# 03_HMS_Input.net
KiCad netlist of a schematic drawn in Altium Designer
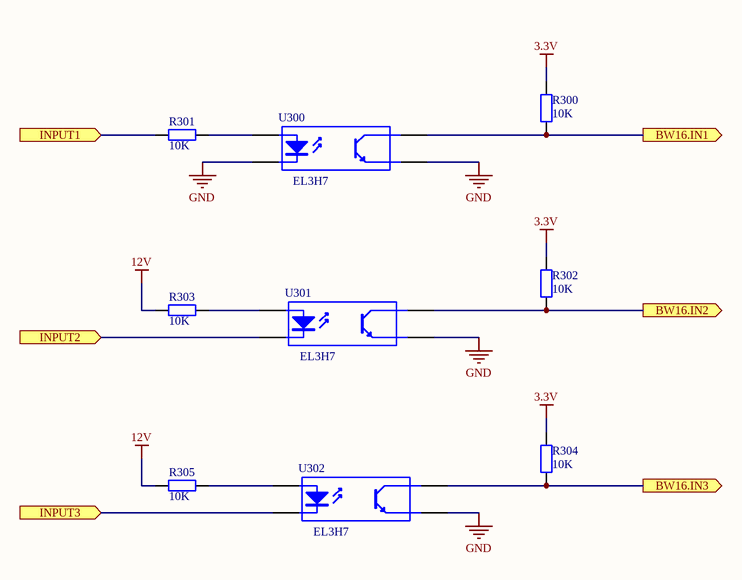
[diagram p0: [03].HMS.Input.SchDoc]

(export (version "E")
  (design (tool "Eeschema 10.0.6"))
  (components
    (comp (ref "R300")
      (value "10K")
      (footprint "RES_0402(1005)")
      (description "RES 10K OHM 5% 1/16W 0402")
      (fields (field (name "MPN") "RC0402JR-074K7P") (field (name "MFR") "YAGEO"))
      (libsource (lib "02.Resistor.0402") (part "RC0402JR-074K7P"))
    )
    (comp (ref "R301")
      (value "10K")
      (footprint "RES_0402(1005)")
      (description "RES 10K OHM 5% 1/16W 0402")
      (fields (field (name "MPN") "RC0402JR-074K7P") (field (name "MFR") "YAGEO"))
      (libsource (lib "02.Resistor.0402") (part "RC0402JR-0710KL"))
    )
    (comp (ref "R302")
      (value "10K")
      (footprint "RES_0402(1005)")
      (description "RES 10K OHM 5% 1/16W 0402")
      (fields (field (name "MPN") "RC0402JR-074K7P") (field (name "MFR") "YAGEO"))
      (libsource (lib "02.Resistor.0402") (part "RC0402JR-074K7P"))
    )
    (comp (ref "R303")
      (value "10K")
      (footprint "RES_0402(1005)")
      (description "RES 10K OHM 5% 1/16W 0402")
      (fields (field (name "MPN") "RC0402JR-074K7P") (field (name "MFR") "YAGEO"))
      (libsource (lib "02.Resistor.0402") (part "RC0402JR-0710KL"))
    )
    (comp (ref "R304")
      (value "10K")
      (footprint "RES_0402(1005)")
      (description "RES 10K OHM 5% 1/16W 0402")
      (fields (field (name "MPN") "RC0402JR-074K7P") (field (name "MFR") "YAGEO"))
      (libsource (lib "02.Resistor.0402") (part "RC0402JR-074K7P"))
    )
    (comp (ref "R305")
      (value "10K")
      (footprint "RES_0402(1005)")
      (description "RES 10K OHM 5% 1/16W 0402")
      (fields (field (name "MPN") "RC0402JR-074K7P") (field (name "MFR") "YAGEO"))
      (libsource (lib "02.Resistor.0402") (part "RC0402JR-0710KL"))
    )
    (comp (ref "U300")
      (value "EL3H7")
      (footprint "Opto small")
      (description "EL3H7 Optoisolator 3.75KV 1CH 4-SSOP")
      (fields
        (field (name "MANUFACTURER") "Vishay Semiconductors")
        (field (name "MANUFACTURER PART NUMBER") "VOM617A-2T")
      )
      (libsource (lib "20.OtherPassive") (part "Optocouplers"))
    )
    (comp (ref "U301")
      (value "EL3H7")
      (footprint "Opto small")
      (description "EL3H7 Optoisolator 3.75KV 1CH 4-SSOP")
      (fields
        (field (name "MANUFACTURER") "Vishay Semiconductors")
        (field (name "MANUFACTURER PART NUMBER") "VOM617A-2T")
      )
      (libsource (lib "20.OtherPassive") (part "Optocouplers"))
    )
    (comp (ref "U302")
      (value "EL3H7")
      (footprint "Opto small")
      (description "EL3H7 Optoisolator 3.75KV 1CH 4-SSOP")
      (fields
        (field (name "MANUFACTURER") "Vishay Semiconductors")
        (field (name "MANUFACTURER PART NUMBER") "VOM617A-2T")
      )
      (libsource (lib "20.OtherPassive") (part "Optocouplers"))
    )
  )
  (nets
    (net (code "1") (name "/BW16.IN1") (class "Default")
      (node (ref "R300") (pin "1") (pinfunction "1_1") (pintype "passive"))
      (node (ref "U300") (pin "4") (pinfunction "4_4") (pintype "passive"))
    )
    (net (code "2") (name "/BW16.IN2") (class "Default")
      (node (ref "R302") (pin "1") (pinfunction "1_1") (pintype "passive"))
      (node (ref "U301") (pin "4") (pinfunction "4_4") (pintype "passive"))
    )
    (net (code "3") (name "/BW16.IN3") (class "Default")
      (node (ref "R304") (pin "1") (pinfunction "1_1") (pintype "passive"))
      (node (ref "U302") (pin "4") (pinfunction "4_4") (pintype "passive"))
    )
    (net (code "4") (name "/INPUT1") (class "Default")
      (node (ref "R301") (pin "1") (pinfunction "1_1") (pintype "passive"))
    )
    (net (code "5") (name "/INPUT2") (class "Default")
      (node (ref "U301") (pin "2") (pinfunction "2_2") (pintype "passive"))
    )
    (net (code "6") (name "/INPUT3") (class "Default")
      (node (ref "U302") (pin "2") (pinfunction "2_2") (pintype "passive"))
    )
    (net (code "7") (name "3.3V") (class "Default")
      (node (ref "R300") (pin "2") (pinfunction "2_2") (pintype "passive"))
      (node (ref "R302") (pin "2") (pinfunction "2_2") (pintype "passive"))
      (node (ref "R304") (pin "2") (pinfunction "2_2") (pintype "passive"))
    )
    (net (code "8") (name "12V") (class "Default")
      (node (ref "R303") (pin "1") (pinfunction "1_1") (pintype "passive"))
      (node (ref "R305") (pin "1") (pinfunction "1_1") (pintype "passive"))
    )
    (net (code "9") (name "GND") (class "Default")
      (node (ref "U300") (pin "2") (pinfunction "2_2") (pintype "passive"))
      (node (ref "U300") (pin "3") (pinfunction "3_3") (pintype "passive"))
      (node (ref "U301") (pin "3") (pinfunction "3_3") (pintype "passive"))
      (node (ref "U302") (pin "3") (pinfunction "3_3") (pintype "passive"))
    )
    (net (code "10") (name "Net-(R301-Pad2)") (class "Default")
      (node (ref "R301") (pin "2") (pinfunction "2_2") (pintype "passive"))
      (node (ref "U300") (pin "1") (pinfunction "1_1") (pintype "passive"))
    )
    (net (code "11") (name "Net-(R303-Pad2)") (class "Default")
      (node (ref "R303") (pin "2") (pinfunction "2_2") (pintype "passive"))
      (node (ref "U301") (pin "1") (pinfunction "1_1") (pintype "passive"))
    )
    (net (code "12") (name "Net-(R305-Pad2)") (class "Default")
      (node (ref "R305") (pin "2") (pinfunction "2_2") (pintype "passive"))
      (node (ref "U302") (pin "1") (pinfunction "1_1") (pintype "passive"))
    )
  )
)
